# ReceiverPCB.net
KiCad netlist of a schematic drawn in EAGLE
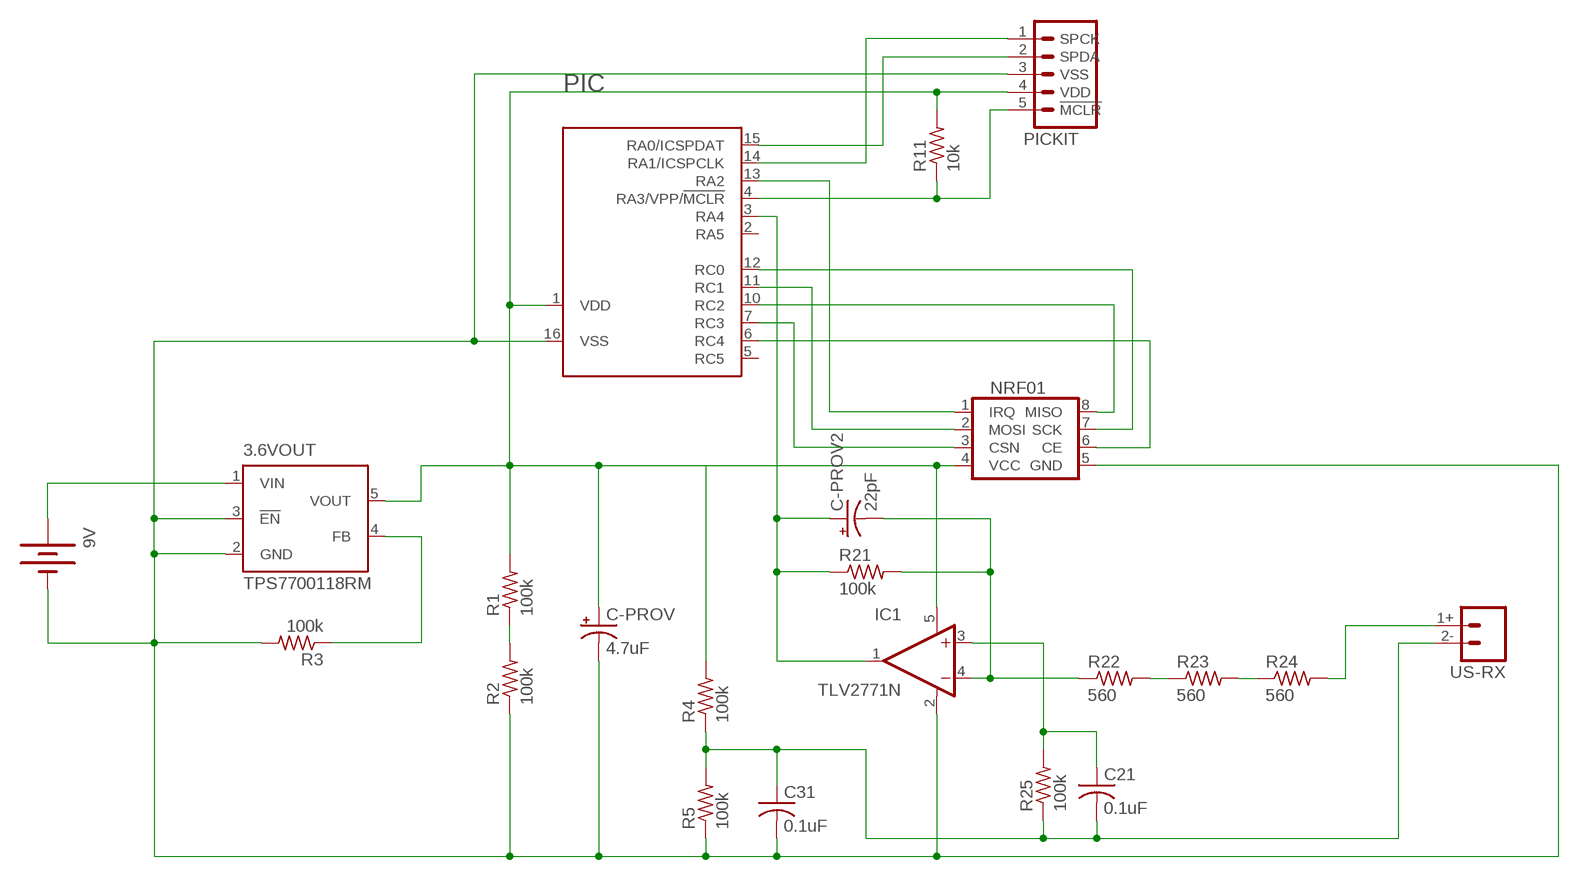
[diagram p0: schematic, sheet 1]

(export (version "E")
  (design (tool "Eeschema 10.0.6"))
  (components
    (comp (ref "3.6VOUT")
      (value "TPS7700118RM")
      (footprint "eagle-import:SOT23-5L")
      (libsource (lib "eagle-import") (part "TPS77001M18R"))
    )
    (comp (ref "9V")
      (value "BATTERY9V")
      (footprint "eagle-import:BATTCON_9V")
      (libsource (lib "eagle-import") (part "BATTERY9V"))
    )
    (comp (ref "C-PROV")
      (value "4.7uF")
      (footprint "eagle-import:E2,5-6E")
      (libsource (lib "eagle-import") (part "CPOL-USE2,5-6E"))
    )
    (comp (ref "C-PROV2")
      (value "22pF")
      (footprint "eagle-import:E2,5-6E")
      (libsource (lib "eagle-import") (part "CPOL-USE2,5-6E"))
    )
    (comp (ref "C21")
      (value "0.1uF")
      (footprint "eagle-import:C0805")
      (libsource (lib "eagle-import") (part "C-USC0805"))
    )
    (comp (ref "C31")
      (value "0.1uF")
      (footprint "eagle-import:C0805")
      (libsource (lib "eagle-import") (part "C-USC0805"))
    )
    (comp (ref "IC1")
      (value "TLV2771N")
      (footprint "eagle-import:SOT23-5")
      (fields (field (name "MF") "TEXAS INSTRUMENTS") (field (name "MPN") "OPA237NA/250"))
      (libsource (lib "eagle-import") (part "TLV2771N"))
    )
    (comp (ref "NRF01")
      (value "NRF01")
      (footprint "eagle-import:JP4Q")
      (libsource (lib "eagle-import") (part "NRF01"))
    )
    (comp (ref "PIC")
      (value "PIC16F1503(DIL16)")
      (footprint "eagle-import:DIL16")
      (libsource (lib "eagle-import") (part "PIC16F1503(DIL16)"))
    )
    (comp (ref "PICKIT")
      (value "M05PTH")
      (footprint "eagle-import:1X05")
      (libsource (lib "eagle-import") (part "M05PTH"))
    )
    (comp (ref "R1")
      (value "100k")
      (footprint "eagle-import:R0805")
      (libsource (lib "eagle-import") (part "R-US_R0805"))
    )
    (comp (ref "R2")
      (value "100k")
      (footprint "eagle-import:R0805")
      (libsource (lib "eagle-import") (part "R-US_R0805"))
    )
    (comp (ref "R3")
      (value "100k")
      (footprint "eagle-import:R0805")
      (libsource (lib "eagle-import") (part "R-US_R0805"))
    )
    (comp (ref "R4")
      (value "100k")
      (footprint "eagle-import:R0805")
      (libsource (lib "eagle-import") (part "R-US_R0805"))
    )
    (comp (ref "R5")
      (value "100k")
      (footprint "eagle-import:R0805")
      (libsource (lib "eagle-import") (part "R-US_R0805"))
    )
    (comp (ref "R11")
      (value "10k")
      (footprint "eagle-import:R0805")
      (libsource (lib "eagle-import") (part "R-US_R0805"))
    )
    (comp (ref "R21")
      (value "100k")
      (footprint "eagle-import:R0805")
      (libsource (lib "eagle-import") (part "R-US_R0805"))
    )
    (comp (ref "R22")
      (value "560")
      (footprint "eagle-import:R0805")
      (libsource (lib "eagle-import") (part "R-US_R0805"))
    )
    (comp (ref "R23")
      (value "560")
      (footprint "eagle-import:R0805")
      (libsource (lib "eagle-import") (part "R-US_R0805"))
    )
    (comp (ref "R24")
      (value "560")
      (footprint "eagle-import:R0805")
      (libsource (lib "eagle-import") (part "R-US_R0805"))
    )
    (comp (ref "R25")
      (value "100k")
      (footprint "eagle-import:R0805")
      (libsource (lib "eagle-import") (part "R-US_R0805"))
    )
    (comp (ref "US-RX")
      (value "M02UT-1640K-TT-2-R")
      (footprint "eagle-import:ULTRASONIC-PEIZO")
      (libsource (lib "eagle-import") (part "M02UT-1640K-TT-2-R"))
    )
  )
  (nets
    (net (code "1") (name "Net-(3.6VOUT-FB)") (class "Default")
      (node (ref "3.6VOUT") (pin "4") (pinfunction "FB_4") (pintype "passive"))
      (node (ref "R3") (pin "1") (pinfunction "1_1") (pintype "passive"))
    )
    (net (code "2") (name "Net-(3.6VOUT-GND)") (class "Default")
      (node (ref "3.6VOUT") (pin "2") (pinfunction "GND_2") (pintype "power_in"))
      (node (ref "3.6VOUT") (pin "3") (pinfunction "~{EN}_3") (pintype "input"))
      (node (ref "9V") (pin "-") (pinfunction "-_-") (pintype "power_in"))
      (node (ref "C-PROV") (pin "-") (pinfunction "-_-") (pintype "passive"))
      (node (ref "C31") (pin "2") (pinfunction "2_2") (pintype "passive"))
      (node (ref "IC1") (pin "2") (pinfunction "V-_2") (pintype "power_in"))
      (node (ref "NRF01") (pin "5") (pinfunction "GND_5") (pintype "passive"))
      (node (ref "PIC") (pin "16") (pinfunction "VSS_16") (pintype "bidirectional"))
      (node (ref "PICKIT") (pin "3") (pinfunction "VSS_3") (pintype "passive"))
      (node (ref "R2") (pin "1") (pinfunction "1_1") (pintype "passive"))
      (node (ref "R3") (pin "2") (pinfunction "2_2") (pintype "passive"))
      (node (ref "R5") (pin "1") (pinfunction "1_1") (pintype "passive"))
    )
    (net (code "3") (name "Net-(3.6VOUT-VIN)") (class "Default")
      (node (ref "3.6VOUT") (pin "1") (pinfunction "VIN_1") (pintype "input"))
      (node (ref "9V") (pin "+") (pinfunction "+_+") (pintype "power_in"))
    )
    (net (code "4") (name "Net-(3.6VOUT-VOUT)") (class "Default")
      (node (ref "3.6VOUT") (pin "5") (pinfunction "VOUT_5") (pintype "output"))
      (node (ref "C-PROV") (pin "+") (pinfunction "+_+") (pintype "passive"))
      (node (ref "IC1") (pin "5") (pinfunction "V+_5") (pintype "power_in"))
      (node (ref "NRF01") (pin "4") (pinfunction "VCC_4") (pintype "passive"))
      (node (ref "PIC") (pin "1") (pinfunction "VDD_1") (pintype "bidirectional"))
      (node (ref "PICKIT") (pin "4") (pinfunction "VDD_4") (pintype "passive"))
      (node (ref "R1") (pin "2") (pinfunction "2_2") (pintype "passive"))
      (node (ref "R11") (pin "2") (pinfunction "2_2") (pintype "passive"))
      (node (ref "R4") (pin "2") (pinfunction "2_2") (pintype "passive"))
    )
    (net (code "5") (name "Net-(IC1-+IN)") (class "Default")
      (node (ref "C21") (pin "1") (pinfunction "1_1") (pintype "passive"))
      (node (ref "IC1") (pin "3") (pinfunction "+IN_3") (pintype "input"))
      (node (ref "R25") (pin "2") (pinfunction "2_2") (pintype "passive"))
    )
    (net (code "6") (name "Net-(IC1--IN)") (class "Default")
      (node (ref "C-PROV2") (pin "-") (pinfunction "-_-") (pintype "passive"))
      (node (ref "IC1") (pin "4") (pinfunction "-IN_4") (pintype "input"))
      (node (ref "R21") (pin "2") (pinfunction "2_2") (pintype "passive"))
      (node (ref "R22") (pin "1") (pinfunction "1_1") (pintype "passive"))
    )
    (net (code "7") (name "Net-(IC1-OUT)") (class "Default")
      (node (ref "C-PROV2") (pin "+") (pinfunction "+_+") (pintype "passive"))
      (node (ref "IC1") (pin "1") (pinfunction "OUT_1") (pintype "output"))
      (node (ref "PIC") (pin "3") (pinfunction "RA4_3") (pintype "bidirectional"))
      (node (ref "R21") (pin "1") (pinfunction "1_1") (pintype "passive"))
    )
    (net (code "8") (name "Net-(NRF01-CE)") (class "Default")
      (node (ref "NRF01") (pin "6") (pinfunction "CE_6") (pintype "passive"))
      (node (ref "PIC") (pin "6") (pinfunction "RC4_6") (pintype "bidirectional"))
    )
    (net (code "9") (name "Net-(NRF01-CSN)") (class "Default")
      (node (ref "NRF01") (pin "3") (pinfunction "CSN_3") (pintype "passive"))
      (node (ref "PIC") (pin "7") (pinfunction "RC3_7") (pintype "bidirectional"))
    )
    (net (code "10") (name "Net-(NRF01-IRQ)") (class "Default")
      (node (ref "NRF01") (pin "1") (pinfunction "IRQ_1") (pintype "passive"))
      (node (ref "PIC") (pin "13") (pinfunction "RA2_13") (pintype "bidirectional"))
    )
    (net (code "11") (name "Net-(NRF01-MISO)") (class "Default")
      (node (ref "NRF01") (pin "8") (pinfunction "MISO_8") (pintype "passive"))
      (node (ref "PIC") (pin "10") (pinfunction "RC2_10") (pintype "bidirectional"))
    )
    (net (code "12") (name "Net-(NRF01-MOSI)") (class "Default")
      (node (ref "NRF01") (pin "2") (pinfunction "MOSI_2") (pintype "passive"))
      (node (ref "PIC") (pin "11") (pinfunction "RC1_11") (pintype "bidirectional"))
    )
    (net (code "13") (name "Net-(NRF01-SCK)") (class "Default")
      (node (ref "NRF01") (pin "7") (pinfunction "SCK_7") (pintype "passive"))
      (node (ref "PIC") (pin "12") (pinfunction "RC0_12") (pintype "bidirectional"))
    )
    (net (code "14") (name "Net-(PIC-RA0{slash}ICSPDAT)") (class "Default")
      (node (ref "PIC") (pin "15") (pinfunction "RA0/ICSPDAT_15") (pintype "bidirectional"))
      (node (ref "PICKIT") (pin "2") (pinfunction "SPDA_2") (pintype "passive"))
    )
    (net (code "15") (name "Net-(PIC-RA1{slash}ICSPCLK)") (class "Default")
      (node (ref "PIC") (pin "14") (pinfunction "RA1/ICSPCLK_14") (pintype "bidirectional"))
      (node (ref "PICKIT") (pin "1") (pinfunction "SPCK_1") (pintype "passive"))
    )
    (net (code "16") (name "Net-(PIC-RA3{slash}VPP{slash}~{MCLR})") (class "Default")
      (node (ref "PIC") (pin "4") (pinfunction "RA3/VPP/~{MCLR}_4") (pintype "bidirectional"))
      (node (ref "PICKIT") (pin "5") (pinfunction "~{MCLR}_5") (pintype "passive"))
      (node (ref "R11") (pin "1") (pinfunction "1_1") (pintype "passive"))
    )
    (net (code "17") (name "Net-(R1-Pad1)") (class "Default")
      (node (ref "R1") (pin "1") (pinfunction "1_1") (pintype "passive"))
      (node (ref "R2") (pin "2") (pinfunction "2_2") (pintype "passive"))
    )
    (net (code "18") (name "Net-(R22-Pad2)") (class "Default")
      (node (ref "R22") (pin "2") (pinfunction "2_2") (pintype "passive"))
      (node (ref "R23") (pin "1") (pinfunction "1_1") (pintype "passive"))
    )
    (net (code "19") (name "Net-(R23-Pad2)") (class "Default")
      (node (ref "R23") (pin "2") (pinfunction "2_2") (pintype "passive"))
      (node (ref "R24") (pin "1") (pinfunction "1_1") (pintype "passive"))
    )
    (net (code "20") (name "Net-(US-RX-1)") (class "Default")
      (node (ref "R24") (pin "2") (pinfunction "2_2") (pintype "passive"))
      (node (ref "US-RX") (pin "1+") (pinfunction "1_1+") (pintype "passive"))
    )
    (net (code "21") (name "Net-(US-RX-2)") (class "Default")
      (node (ref "C21") (pin "2") (pinfunction "2_2") (pintype "passive"))
      (node (ref "C31") (pin "1") (pinfunction "1_1") (pintype "passive"))
      (node (ref "R25") (pin "1") (pinfunction "1_1") (pintype "passive"))
      (node (ref "R4") (pin "1") (pinfunction "1_1") (pintype "passive"))
      (node (ref "R5") (pin "2") (pinfunction "2_2") (pintype "passive"))
      (node (ref "US-RX") (pin "2-") (pinfunction "2_2-") (pintype "passive"))
    )
    (net (code "22") (name "unconnected-(PIC-RA5-Pad2)") (class "Default")
      (node (ref "PIC") (pin "2") (pinfunction "RA5_2") (pintype "bidirectional"))
    )
    (net (code "23") (name "unconnected-(PIC-RC5-Pad5)") (class "Default")
      (node (ref "PIC") (pin "5") (pinfunction "RC5_5") (pintype "bidirectional"))
    )
  )
)
